# design.net
KiCad netlist of a schematic drawn in Altium Designer
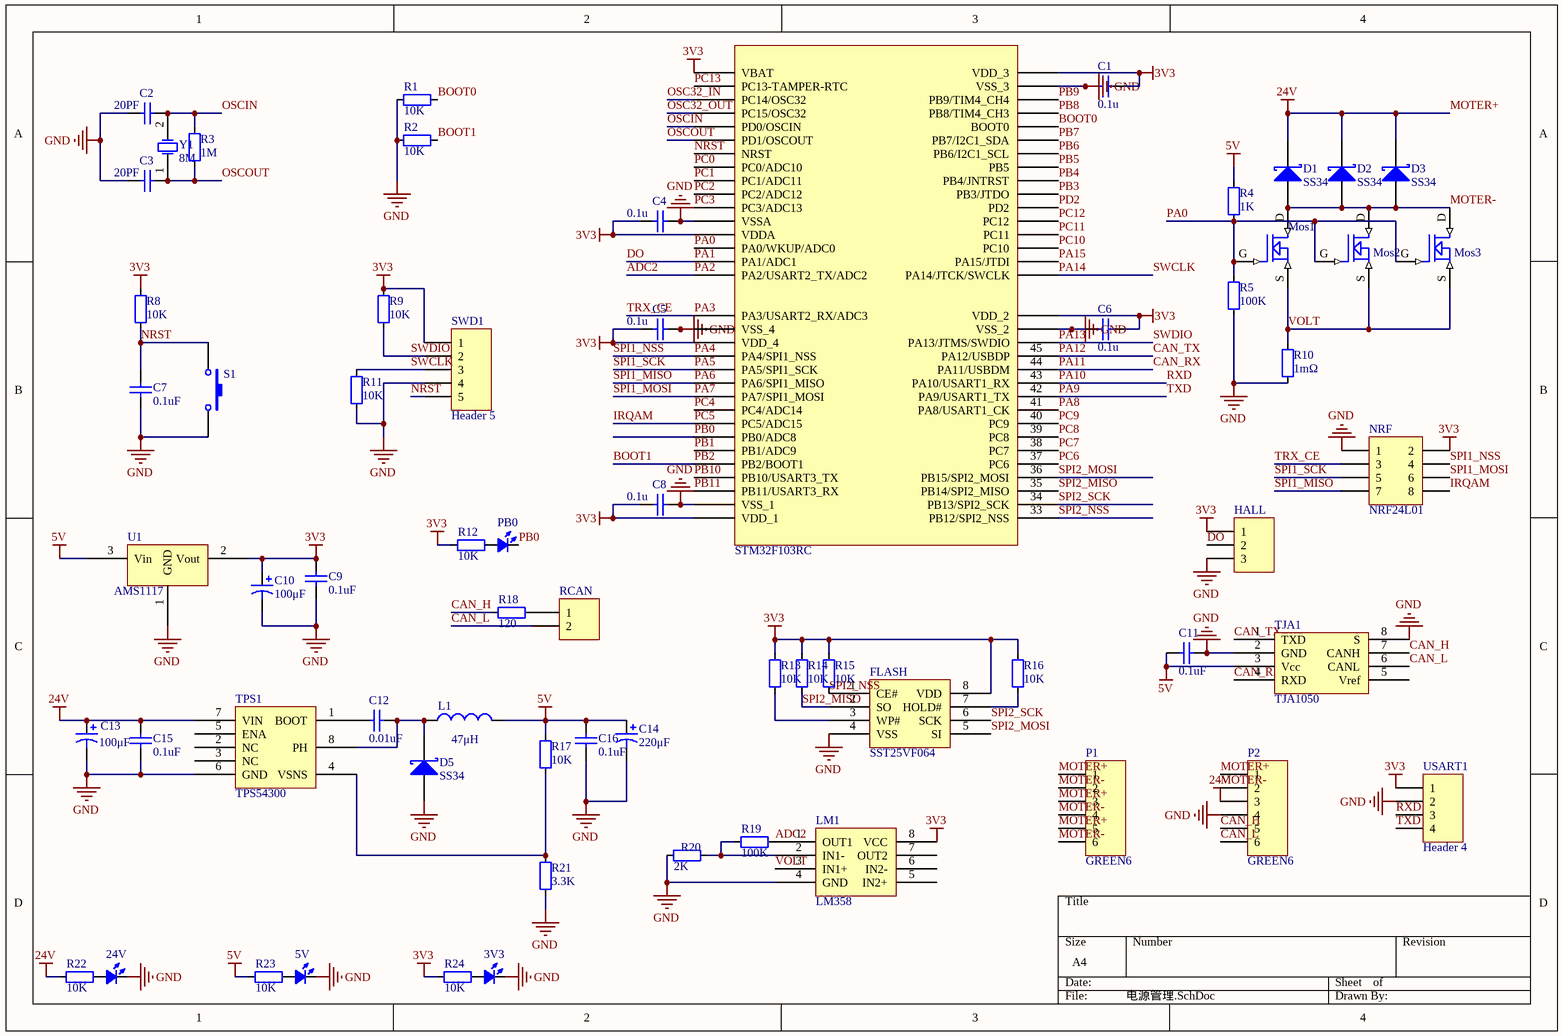
[diagram p0: 电源管理.SchDoc]

(export (version "E")
  (design (tool "Eeschema 10.0.6"))
  (components
    (comp (ref "3V3")
      (value "LED_0603")
      (footprint "LED_0805_GREEN")
      (description "LED")
      (libsource (lib "Integrated_Library") (part "LED_0603"))
    )
    (comp (ref "5V")
      (value "LED_0603")
      (footprint "LED_0805_GREEN")
      (description "LED")
      (libsource (lib "Integrated_Library") (part "LED_0603"))
    )
    (comp (ref "24V")
      (value "LED_0603")
      (footprint "LED_0805_GREEN")
      (description "LED")
      (libsource (lib "Integrated_Library") (part "LED_0603"))
    )
    (comp (ref "C1")
      (value "0.1u")
      (footprint "CAP-MLCC-0603")
      (description "Capacitor")
      (fields (field (name "Comment") "Cap") (field (name "PUBLISHER") "Altium Limited"))
      (libsource (lib "K60-mainboard-v3.1") (part "Cap_1"))
    )
    (comp (ref "C2")
      (value "20PF")
      (footprint "CAP-MLCC-0603")
      (description "Capacitor")
      (fields (field (name "Comment") "Cap") (field (name "PUBLISHER") "Altium Limited"))
      (libsource (lib "K60-mainboard-v3.1") (part "Cap_1"))
    )
    (comp (ref "C3")
      (value "20PF")
      (footprint "CAP-MLCC-0603")
      (description "Capacitor")
      (fields (field (name "Comment") "Cap") (field (name "PUBLISHER") "Altium Limited"))
      (libsource (lib "K60-mainboard-v3.1") (part "Cap_1"))
    )
    (comp (ref "C4")
      (value "0.1u")
      (footprint "CAP-MLCC-0603")
      (description "Capacitor")
      (fields (field (name "Comment") "Cap") (field (name "PUBLISHER") "Altium Limited"))
      (libsource (lib "K60-mainboard-v3.1") (part "Cap_1"))
    )
    (comp (ref "C5")
      (value "0.1u")
      (footprint "CAP-MLCC-0603")
      (description "Capacitor")
      (fields (field (name "Comment") "Cap") (field (name "PUBLISHER") "Altium Limited"))
      (libsource (lib "K60-mainboard-v3.1") (part "Cap_1"))
    )
    (comp (ref "C6")
      (value "0.1u")
      (footprint "CAP-MLCC-0603")
      (description "Capacitor")
      (fields (field (name "Comment") "Cap") (field (name "PUBLISHER") "Altium Limited"))
      (libsource (lib "K60-mainboard-v3.1") (part "Cap_1"))
    )
    (comp (ref "C7")
      (value "0.1uF")
      (footprint "CAP-MLCC-0603")
      (description "Capacitor")
      (fields (field (name "Comment") "Cap") (field (name "PUBLISHER") "Altium Limited"))
      (libsource (lib "K60-mainboard-v3.1") (part "Cap"))
    )
    (comp (ref "C8")
      (value "0.1u")
      (footprint "CAP-MLCC-0603")
      (description "Capacitor")
      (fields (field (name "Comment") "Cap") (field (name "PUBLISHER") "Altium Limited"))
      (libsource (lib "K60-mainboard-v3.1") (part "Cap_1"))
    )
    (comp (ref "C9")
      (value "0.1uF")
      (footprint "CAP-MLCC-0603")
      (description "Capacitor")
      (fields (field (name "Comment") "Cap") (field (name "PUBLISHER") "Altium Limited"))
      (libsource (lib "K60-mainboard-v3.1") (part "Cap"))
    )
    (comp (ref "C10")
      (value "100μF")
      (footprint "CAP-TAN-3216/CAPA")
      (description "钽电容")
      (fields (field (name "PUBLISHER") "Altium Limited"))
      (libsource (lib "Libraries_2014_0618") (part "CAP-TAN"))
    )
    (comp (ref "C11")
      (value "0.1uF")
      (footprint "CAP-MLCC-0603")
      (description "Capacitor")
      (fields (field (name "Comment") "Cap") (field (name "PUBLISHER") "Altium Limited"))
      (libsource (lib "K60-mainboard-v3.1") (part "Cap"))
    )
    (comp (ref "C12")
      (value "0.01uF")
      (footprint "CAP-MLCC-0603")
      (description "Capacitor")
      (fields (field (name "Comment") "Cap") (field (name "PUBLISHER") "Altium Limited"))
      (libsource (lib "K60-mainboard-v3.1") (part "Cap"))
    )
    (comp (ref "C13")
      (value "100μF")
      (footprint "C5:C5")
      (description "钽电容")
      (fields (field (name "PUBLISHER") "Altium Limited"))
      (libsource (lib "Libraries_2014_0618") (part "CAP-TAN"))
    )
    (comp (ref "C14")
      (value "220μF")
      (footprint "CAP-TAN-7343/CAPD")
      (description "钽电容")
      (fields (field (name "PUBLISHER") "Altium Limited"))
      (libsource (lib "Libraries_2014_0618") (part "CAP-TAN"))
    )
    (comp (ref "C15")
      (value "0.1uF")
      (footprint "CAP-MLCC-0603")
      (description "Capacitor")
      (fields (field (name "Comment") "Cap") (field (name "PUBLISHER") "Altium Limited"))
      (libsource (lib "K60-mainboard-v3.1") (part "Cap"))
    )
    (comp (ref "C16")
      (value "0.1uF")
      (footprint "CAP-MLCC-0603")
      (description "Capacitor")
      (fields (field (name "Comment") "Cap") (field (name "PUBLISHER") "Altium Limited"))
      (libsource (lib "K60-mainboard-v3.1") (part "Cap"))
    )
    (comp (ref "D1")
      (value "SS34")
      (footprint "DO-214AC")
      (description "肖特基二极管")
      (fields (field (name "PUBLISHER") "Altium Limited"))
      (libsource (lib "Libraries_2014_0618") (part "DIODE-Schottky"))
    )
    (comp (ref "D2")
      (value "SS34")
      (footprint "DO-214AC")
      (description "肖特基二极管")
      (fields (field (name "PUBLISHER") "Altium Limited"))
      (libsource (lib "Libraries_2014_0618") (part "DIODE-Schottky"))
    )
    (comp (ref "D3")
      (value "SS34")
      (footprint "DO-214AC")
      (description "肖特基二极管")
      (fields (field (name "PUBLISHER") "Altium Limited"))
      (libsource (lib "Libraries_2014_0618") (part "DIODE-Schottky"))
    )
    (comp (ref "D5")
      (value "SS34")
      (footprint "DO-214AC")
      (description "肖特基二极管")
      (fields (field (name "PUBLISHER") "Altium Limited"))
      (libsource (lib "Libraries_2014_0618") (part "DIODE-Schottky"))
    )
    (comp (ref "FLASH")
      (value "SST25VF064")
      (footprint "SOIC_E200_8")
      (libsource (lib "SST25VF064") (part "Component_1"))
    )
    (comp (ref "HALL")
      (value "Header 3")
      (footprint "HDR1X3")
      (description "Header, 3-Pin")
      (fields (field (name "PUBLISHER") "Altium Limited"))
      (libsource (lib "Libraries_2014_0618") (part "Header 3"))
    )
    (comp (ref "L1")
      (value "47μH")
      (footprint "Integrated_Library:IND_CD32")
      (description "Inductor")
      (fields (field (name "PUBLISHER") "Altium Limited"))
      (libsource (lib "Miscellaneous Devices") (part "Inductor"))
    )
    (comp (ref "LM1")
      (value "LM358")
      (footprint "PCB_IntegratedCircuit:SOP_E150_8")
      (libsource (lib "LM358") (part "Component_1"))
    )
    (comp (ref "Mos1")
      (value "MOSFET N")
      (footprint "Integrated_Library:TO-252AA")
      (description "MOS SOT23")
      (libsource (lib "Integrated_Library") (part "MOSFET N"))
    )
    (comp (ref "Mos2")
      (value "MOSFET N")
      (footprint "Integrated_Library:TO-252AA")
      (description "MOS SOT23")
      (libsource (lib "Integrated_Library") (part "MOSFET N"))
    )
    (comp (ref "Mos3")
      (value "MOSFET N")
      (footprint "Integrated_Library:TO-252AA")
      (description "MOS SOT23")
      (libsource (lib "Integrated_Library") (part "MOSFET N"))
    )
    (comp (ref "NRF")
      (value "NRF24L01")
      (footprint "HDR2X4")
      (description "Header, 4-Pin, Dual row")
      (fields (field (name "PUBLISHER") "Altium Limited"))
      (libsource (lib "Miscellaneous Connectors") (part "MHDR2X4"))
    )
    (comp (ref "P1")
      (value "GREEN6")
      (footprint "Green_6P")
      (description "Header, 6-Pin")
      (fields (field (name "PUBLISHER") "Altium Limited"))
      (libsource (lib "Libraries_2014_0618") (part "Header 6"))
    )
    (comp (ref "P2")
      (value "GREEN6")
      (footprint "Green_6P")
      (description "Header, 6-Pin")
      (fields (field (name "PUBLISHER") "Altium Limited"))
      (libsource (lib "Libraries_2014_0618") (part "Header 6"))
    )
    (comp (ref "PB0")
      (value "LED_0603")
      (footprint "LED_0805_GREEN")
      (description "LED")
      (libsource (lib "Integrated_Library") (part "LED_0603"))
    )
    (comp (ref "R1")
      (value "10K")
      (footprint "RES-0603")
      (description "Resistor")
      (fields (field (name "Comment") "Res_0603"))
      (libsource (lib "Integrated_Library") (part "Res_0603"))
    )
    (comp (ref "R2")
      (value "10K")
      (footprint "RES-0603")
      (description "Resistor")
      (fields (field (name "Comment") "Res_0603"))
      (libsource (lib "Integrated_Library") (part "Res_0603"))
    )
    (comp (ref "R3")
      (value "1M")
      (footprint "RES-0603")
      (description "Resistor")
      (fields (field (name "Comment") "Res_0603"))
      (libsource (lib "") (part "Res_0603_1"))
    )
    (comp (ref "R4")
      (value "1K")
      (footprint "RES-0603")
      (description "Resistor")
      (fields (field (name "Comment") "Res_0603"))
      (libsource (lib "") (part "Res_0603_1"))
    )
    (comp (ref "R5")
      (value "100K")
      (footprint "RES-0603")
      (description "Resistor")
      (fields (field (name "Comment") "Res_0603"))
      (libsource (lib "") (part "Res_0603_1"))
    )
    (comp (ref "R8")
      (value "10K")
      (footprint "RES-0603")
      (description "Resistor")
      (fields (field (name "Comment") "Res_0603"))
      (libsource (lib "") (part "Res_0603_1"))
    )
    (comp (ref "R9")
      (value "10K")
      (footprint "RES-0603")
      (description "Resistor")
      (fields (field (name "Comment") "Res_0603"))
      (libsource (lib "") (part "Res_0603_1"))
    )
    (comp (ref "R10")
      (value "1mΩ")
      (footprint "RESC6332")
      (description "Resistor")
      (fields (field (name "Comment") "Res_0603"))
      (libsource (lib "") (part "Res_0603_1"))
    )
    (comp (ref "R11")
      (value "10K")
      (footprint "RES-0603")
      (description "Resistor")
      (fields (field (name "Comment") "Res_0603"))
      (libsource (lib "") (part "Res_0603_1"))
    )
    (comp (ref "R12")
      (value "10K")
      (footprint "RES-0603")
      (description "Resistor")
      (fields (field (name "Comment") "Res_0603"))
      (libsource (lib "Integrated_Library") (part "Res_0603"))
    )
    (comp (ref "R13")
      (value "10K")
      (footprint "RES-0603")
      (description "Resistor")
      (fields (field (name "Comment") "Res_0603"))
      (libsource (lib "") (part "Res_0603_1"))
    )
    (comp (ref "R14")
      (value "10K")
      (footprint "RES-0603")
      (description "Resistor")
      (fields (field (name "Comment") "Res_0603"))
      (libsource (lib "") (part "Res_0603_1"))
    )
    (comp (ref "R15")
      (value "10K")
      (footprint "RES-0603")
      (description "Resistor")
      (fields (field (name "Comment") "Res_0603"))
      (libsource (lib "") (part "Res_0603_1"))
    )
    (comp (ref "R16")
      (value "10K")
      (footprint "RES-0603")
      (description "Resistor")
      (fields (field (name "Comment") "Res_0603"))
      (libsource (lib "") (part "Res_0603_1"))
    )
    (comp (ref "R17")
      (value "10K")
      (footprint "RES-0603")
      (description "Resistor")
      (fields (field (name "Comment") "Res_0603"))
      (libsource (lib "") (part "Res_0603_1"))
    )
    (comp (ref "R18")
      (value "120")
      (footprint "RES-0603")
      (description "Resistor")
      (fields (field (name "Comment") "Res_0603"))
      (libsource (lib "Integrated_Library") (part "Res_0603"))
    )
    (comp (ref "R19")
      (value "100K")
      (footprint "RES-0603")
      (description "Resistor")
      (fields (field (name "Comment") "Res_0603"))
      (libsource (lib "") (part "Res_0603_3"))
    )
    (comp (ref "R20")
      (value "2K")
      (footprint "RES-0603")
      (description "Resistor")
      (fields (field (name "Comment") "Res_0603"))
      (libsource (lib "") (part "Res_0603_3"))
    )
    (comp (ref "R21")
      (value "3.3K")
      (footprint "RES-0603")
      (description "Resistor")
      (fields (field (name "Comment") "Res_0603"))
      (libsource (lib "") (part "Res_0603_2"))
    )
    (comp (ref "R22")
      (value "10K")
      (footprint "RES-0603")
      (description "Resistor")
      (fields (field (name "Comment") "Res_0603"))
      (libsource (lib "Integrated_Library") (part "Res_0603"))
    )
    (comp (ref "R23")
      (value "10K")
      (footprint "RES-0603")
      (description "Resistor")
      (fields (field (name "Comment") "Res_0603"))
      (libsource (lib "Integrated_Library") (part "Res_0603"))
    )
    (comp (ref "R24")
      (value "10K")
      (footprint "RES-0603")
      (description "Resistor")
      (fields (field (name "Comment") "Res_0603"))
      (libsource (lib "Integrated_Library") (part "Res_0603"))
    )
    (comp (ref "RCAN")
      (value "~")
      (footprint "HDR1X2")
      (description "Header, 2-Pin")
      (fields (field (name "PUBLISHER") "Altium Limited"))
      (libsource (lib "Miscellaneous Connectors") (part "Header 2"))
    )
    (comp (ref "S1")
      (value "SW-PB")
      (footprint "PCB_Switch:KEY_SMD")
      (description "按钮")
      (fields (field (name "PUBLISHER") "Altium Limited"))
      (libsource (lib "Libraries_2014_0618") (part "SW-PB"))
    )
    (comp (ref "STM32F103RC")
      (value "STM32F103RC")
      (footprint "LQFP_P0.5_64")
      (description "MCU")
      (libsource (lib "Integrated_Library") (part "STM32F103RC"))
    )
    (comp (ref "SWD1")
      (value "Header 5")
      (footprint "HDR1X5")
      (description "Header, 5-Pin")
      (fields (field (name "PUBLISHER") "Altium Limited"))
      (libsource (lib "K60-mainboard-v3.1") (part "Header 5"))
    )
    (comp (ref "TJA1")
      (value "TJA1050")
      (footprint "TJA1050")
      (description "CAN总线收发器")
      (libsource (lib "Libraries_2014_0618") (part "TJA1050"))
    )
    (comp (ref "TPS1")
      (value "TPS54300")
      (footprint "SOP_E150_8")
      (libsource (lib "TPS54300") (part "TPS54300"))
    )
    (comp (ref "U1") (value "AMS1117") (footprint "SOT223-3") (libsource (lib "AMS1117") (part "AMS１１１７")))
    (comp (ref "USART1")
      (value "Header 4")
      (footprint "HDR1X4")
      (description "Header, 4-Pin")
      (fields (field (name "PUBLISHER") "Altium Limited"))
      (libsource (lib "K60-mainboard-v3.1") (part "Header 4"))
    )
    (comp (ref "Y1")
      (value "8M")
      (footprint "Libraries_2014_0618:Osc-6032")
      (description "Crystal Oscillator")
      (fields (field (name "PUBLISHER") "Altium Limited"))
      (libsource (lib "Libraries_2014_0618") (part "C-Osc"))
    )
  )
  (nets
    (net (code "1") (name "/ADC2") (class "Default")
      (node (ref "LM1") (pin "1") (pinfunction "OUT1_1") (pintype "passive"))
      (node (ref "R19") (pin "2") (pinfunction "2_2") (pintype "passive"))
      (node (ref "STM32F103RC") (pin "16") (pinfunction "PA2/USART2_TX/ADC2_16") (pintype "passive"))
    )
    (net (code "2") (name "/BOOT0") (class "Default")
      (node (ref "R1") (pin "1") (pinfunction "1_1") (pintype "passive"))
      (node (ref "STM32F103RC") (pin "60") (pinfunction "BOOT0_60") (pintype "passive"))
    )
    (net (code "3") (name "/BOOT1") (class "Default")
      (node (ref "R2") (pin "1") (pinfunction "1_1") (pintype "passive"))
      (node (ref "STM32F103RC") (pin "28") (pinfunction "PB2/BOOT1_28") (pintype "passive"))
    )
    (net (code "4") (name "/CAN_H") (class "Default")
      (node (ref "P2") (pin "5") (pinfunction "5_5") (pintype "passive"))
      (node (ref "R18") (pin "2") (pinfunction "2_2") (pintype "passive"))
      (node (ref "TJA1") (pin "7") (pinfunction "CANH_7") (pintype "passive"))
    )
    (net (code "5") (name "/CAN_L") (class "Default")
      (node (ref "P2") (pin "6") (pinfunction "6_6") (pintype "passive"))
      (node (ref "RCAN") (pin "2") (pinfunction "2_2") (pintype "passive"))
      (node (ref "TJA1") (pin "6") (pinfunction "CANL_6") (pintype "passive"))
    )
    (net (code "6") (name "/CAN_RX") (class "Default")
      (node (ref "STM32F103RC") (pin "44") (pinfunction "PA11/USBDM_44") (pintype "passive"))
      (node (ref "TJA1") (pin "4") (pinfunction "RXD_4") (pintype "passive"))
    )
    (net (code "7") (name "/CAN_TX") (class "Default")
      (node (ref "STM32F103RC") (pin "45") (pinfunction "PA12/USBDP_45") (pintype "passive"))
      (node (ref "TJA1") (pin "1") (pinfunction "TXD_1") (pintype "passive"))
    )
    (net (code "8") (name "/DO") (class "Default")
      (node (ref "HALL") (pin "2") (pinfunction "2_2") (pintype "passive"))
      (node (ref "STM32F103RC") (pin "15") (pinfunction "PA1/ADC1_15") (pintype "passive"))
    )
    (net (code "9") (name "/IRQAM") (class "Default")
      (node (ref "NRF") (pin "8") (pinfunction "8_8") (pintype "passive"))
      (node (ref "STM32F103RC") (pin "25") (pinfunction "PC5/ADC15_25") (pintype "passive"))
    )
    (net (code "10") (name "/MOTER-") (class "Default")
      (node (ref "D1") (pin "1") (pinfunction "A_1") (pintype "passive"))
      (node (ref "D2") (pin "1") (pinfunction "A_1") (pintype "passive"))
      (node (ref "D3") (pin "1") (pinfunction "A_1") (pintype "passive"))
      (node (ref "Mos1") (pin "D") (pinfunction "D_D") (pintype "input"))
      (node (ref "Mos2") (pin "D") (pinfunction "D_D") (pintype "input"))
      (node (ref "Mos3") (pin "D") (pinfunction "D_D") (pintype "input"))
      (node (ref "P1") (pin "2") (pinfunction "2_2") (pintype "passive"))
      (node (ref "P1") (pin "4") (pinfunction "4_4") (pintype "passive"))
      (node (ref "P1") (pin "6") (pinfunction "6_6") (pintype "passive"))
      (node (ref "P2") (pin "2") (pinfunction "2_2") (pintype "passive"))
    )
    (net (code "11") (name "/NRST") (class "Default")
      (node (ref "C7") (pin "1") (pinfunction "1_1") (pintype "passive"))
      (node (ref "R8") (pin "1") (pinfunction "1_1") (pintype "passive"))
      (node (ref "S1") (pin "1") (pinfunction "1_1") (pintype "passive"))
      (node (ref "STM32F103RC") (pin "7") (pinfunction "NRST_7") (pintype "passive"))
      (node (ref "SWD1") (pin "5") (pinfunction "5_5") (pintype "passive"))
    )
    (net (code "12") (name "/OSC32_IN") (class "Default")
      (node (ref "STM32F103RC") (pin "3") (pinfunction "PC14/OSC32_3") (pintype "passive"))
    )
    (net (code "13") (name "/OSC32_OUT") (class "Default")
      (node (ref "STM32F103RC") (pin "4") (pinfunction "PC15/OSC32_4") (pintype "passive"))
    )
    (net (code "14") (name "/OSCIN") (class "Default")
      (node (ref "C2") (pin "2") (pinfunction "2_2") (pintype "passive"))
      (node (ref "R3") (pin "2") (pinfunction "2_2") (pintype "passive"))
      (node (ref "STM32F103RC") (pin "5") (pinfunction "PD0/OSCIN_5") (pintype "passive"))
      (node (ref "Y1") (pin "2") (pinfunction "OSC2_2") (pintype "passive"))
    )
    (net (code "15") (name "/OSCOUT") (class "Default")
      (node (ref "C3") (pin "2") (pinfunction "2_2") (pintype "passive"))
      (node (ref "R3") (pin "1") (pinfunction "1_1") (pintype "passive"))
      (node (ref "STM32F103RC") (pin "6") (pinfunction "PD1/OSCOUT_6") (pintype "passive"))
      (node (ref "Y1") (pin "1") (pinfunction "OSC1_1") (pintype "passive"))
    )
    (net (code "16") (name "/PA0") (class "Default")
      (node (ref "Mos1") (pin "G") (pinfunction "G_G") (pintype "input"))
      (node (ref "Mos2") (pin "G") (pinfunction "G_G") (pintype "input"))
      (node (ref "Mos3") (pin "G") (pinfunction "G_G") (pintype "input"))
      (node (ref "R4") (pin "1") (pinfunction "1_1") (pintype "passive"))
      (node (ref "R5") (pin "2") (pinfunction "2_2") (pintype "passive"))
      (node (ref "STM32F103RC") (pin "14") (pinfunction "PA0/WKUP/ADC0_14") (pintype "passive"))
    )
    (net (code "17") (name "/PA3") (class "Default")
      (node (ref "NRF") (pin "3") (pinfunction "3_3") (pintype "passive"))
      (node (ref "STM32F103RC") (pin "17") (pinfunction "PA3/USART2_RX/ADC3_17") (pintype "passive"))
    )
    (net (code "18") (name "/PA4") (class "Default")
      (node (ref "NRF") (pin "4") (pinfunction "4_4") (pintype "passive"))
      (node (ref "STM32F103RC") (pin "20") (pinfunction "PA4/SPI1_NSS_20") (pintype "passive"))
    )
    (net (code "19") (name "/PA5") (class "Default")
      (node (ref "NRF") (pin "5") (pinfunction "5_5") (pintype "passive"))
      (node (ref "STM32F103RC") (pin "21") (pinfunction "PA5/SPI1_SCK_21") (pintype "passive"))
    )
    (net (code "20") (name "/PA6") (class "Default")
      (node (ref "NRF") (pin "7") (pinfunction "7_7") (pintype "passive"))
      (node (ref "STM32F103RC") (pin "22") (pinfunction "PA6/SPI1_MISO_22") (pintype "passive"))
    )
    (net (code "21") (name "/PA7") (class "Default")
      (node (ref "NRF") (pin "6") (pinfunction "6_6") (pintype "passive"))
      (node (ref "STM32F103RC") (pin "23") (pinfunction "PA7/SPI1_MOSI_23") (pintype "passive"))
    )
    (net (code "22") (name "/PA8") (class "Default")
      (node (ref "STM32F103RC") (pin "41") (pinfunction "PA8/USART1_CK_41") (pintype "passive"))
    )
    (net (code "23") (name "/PA9") (class "Default")
      (node (ref "STM32F103RC") (pin "42") (pinfunction "PA9/USART1_TX_42") (pintype "passive"))
      (node (ref "USART1") (pin "4") (pinfunction "4_4") (pintype "passive"))
    )
    (net (code "24") (name "/PA10") (class "Default")
      (node (ref "STM32F103RC") (pin "43") (pinfunction "PA10/USART1_RX_43") (pintype "passive"))
      (node (ref "USART1") (pin "3") (pinfunction "3_3") (pintype "passive"))
    )
    (net (code "25") (name "/PA13") (class "Default")
      (node (ref "R9") (pin "1") (pinfunction "1_1") (pintype "passive"))
      (node (ref "STM32F103RC") (pin "46") (pinfunction "PA13/JTMS/SWDIO_46") (pintype "passive"))
      (node (ref "SWD1") (pin "2") (pinfunction "2_2") (pintype "passive"))
    )
    (net (code "26") (name "/PA14") (class "Default")
      (node (ref "R11") (pin "2") (pinfunction "2_2") (pintype "passive"))
      (node (ref "STM32F103RC") (pin "49") (pinfunction "PA14/JTCK/SWCLK_49") (pintype "passive"))
      (node (ref "SWD1") (pin "3") (pinfunction "3_3") (pintype "passive"))
    )
    (net (code "27") (name "/PA15") (class "Default")
      (node (ref "STM32F103RC") (pin "50") (pinfunction "PA15/JTDI_50") (pintype "passive"))
    )
    (net (code "28") (name "/PB0") (class "Default")
      (node (ref "PB0") (pin "2") (pinfunction "K_2") (pintype "passive"))
      (node (ref "STM32F103RC") (pin "26") (pinfunction "PB0/ADC8_26") (pintype "passive"))
    )
    (net (code "29") (name "/PB1") (class "Default")
      (node (ref "STM32F103RC") (pin "27") (pinfunction "PB1/ADC9_27") (pintype "passive"))
    )
    (net (code "30") (name "/PB3") (class "Default")
      (node (ref "STM32F103RC") (pin "55") (pinfunction "PB3/JTDO_55") (pintype "passive"))
    )
    (net (code "31") (name "/PB4") (class "Default")
      (node (ref "STM32F103RC") (pin "56") (pinfunction "PB4/JNTRST_56") (pintype "passive"))
    )
    (net (code "32") (name "/PB5") (class "Default")
      (node (ref "STM32F103RC") (pin "57") (pinfunction "PB5_57") (pintype "passive"))
    )
    (net (code "33") (name "/PB6") (class "Default")
      (node (ref "STM32F103RC") (pin "58") (pinfunction "PB6/I2C1_SCL_58") (pintype "passive"))
    )
    (net (code "34") (name "/PB7") (class "Default")
      (node (ref "STM32F103RC") (pin "59") (pinfunction "PB7/I2C1_SDA_59") (pintype "passive"))
    )
    (net (code "35") (name "/PB8") (class "Default")
      (node (ref "STM32F103RC") (pin "61") (pinfunction "PB8/TIM4_CH3_61") (pintype "passive"))
    )
    (net (code "36") (name "/PB9") (class "Default")
      (node (ref "STM32F103RC") (pin "62") (pinfunction "PB9/TIM4_CH4_62") (pintype "passive"))
    )
    (net (code "37") (name "/PB10") (class "Default")
      (node (ref "STM32F103RC") (pin "29") (pinfunction "PB10/USART3_TX_29") (pintype "passive"))
    )
    (net (code "38") (name "/PB11") (class "Default")
      (node (ref "STM32F103RC") (pin "30") (pinfunction "PB11/USART3_RX_30") (pintype "passive"))
    )
    (net (code "39") (name "/PC0") (class "Default")
      (node (ref "STM32F103RC") (pin "8") (pinfunction "PC0/ADC10_8") (pintype "passive"))
    )
    (net (code "40") (name "/PC1") (class "Default")
      (node (ref "STM32F103RC") (pin "9") (pinfunction "PC1/ADC11_9") (pintype "passive"))
    )
    (net (code "41") (name "/PC2") (class "Default")
      (node (ref "STM32F103RC") (pin "10") (pinfunction "PC2/ADC12_10") (pintype "passive"))
    )
    (net (code "42") (name "/PC3") (class "Default")
      (node (ref "STM32F103RC") (pin "11") (pinfunction "PC3/ADC13_11") (pintype "passive"))
    )
    (net (code "43") (name "/PC4") (class "Default")
      (node (ref "STM32F103RC") (pin "24") (pinfunction "PC4/ADC14_24") (pintype "passive"))
    )
    (net (code "44") (name "/PC6") (class "Default")
      (node (ref "STM32F103RC") (pin "37") (pinfunction "PC6_37") (pintype "passive"))
    )
    (net (code "45") (name "/PC7") (class "Default")
      (node (ref "STM32F103RC") (pin "38") (pinfunction "PC7_38") (pintype "passive"))
    )
    (net (code "46") (name "/PC8") (class "Default")
      (node (ref "STM32F103RC") (pin "39") (pinfunction "PC8_39") (pintype "passive"))
    )
    (net (code "47") (name "/PC9") (class "Default")
      (node (ref "STM32F103RC") (pin "40") (pinfunction "PC9_40") (pintype "passive"))
    )
    (net (code "48") (name "/PC10") (class "Default")
      (node (ref "STM32F103RC") (pin "51") (pinfunction "PC10_51") (pintype "passive"))
    )
    (net (code "49") (name "/PC11") (class "Default")
      (node (ref "STM32F103RC") (pin "52") (pinfunction "PC11_52") (pintype "passive"))
    )
    (net (code "50") (name "/PC12") (class "Default")
      (node (ref "STM32F103RC") (pin "53") (pinfunction "PC12_53") (pintype "passive"))
    )
    (net (code "51") (name "/PC13") (class "Default")
      (node (ref "STM32F103RC") (pin "2") (pinfunction "PC13-TAMPER-RTC_2") (pintype "passive"))
    )
    (net (code "52") (name "/PD2") (class "Default")
      (node (ref "STM32F103RC") (pin "54") (pinfunction "PD2_54") (pintype "passive"))
    )
    (net (code "53") (name "/SPI2_MISO") (class "Default")
      (node (ref "FLASH") (pin "2") (pinfunction "SO_2") (pintype "passive"))
      (node (ref "R14") (pin "1") (pinfunction "1_1") (pintype "passive"))
      (node (ref "STM32F103RC") (pin "35") (pinfunction "PB14/SPI2_MISO_35") (pintype "passive"))
    )
    (net (code "54") (name "/SPI2_MOSI") (class "Default")
      (node (ref "FLASH") (pin "5") (pinfunction "SI_5") (pintype "passive"))
      (node (ref "STM32F103RC") (pin "36") (pinfunction "PB15/SPI2_MOSI_36") (pintype "passive"))
    )
    (net (code "55") (name "/SPI2_NSS") (class "Default")
      (node (ref "FLASH") (pin "1") (pinfunction "CE#_1") (pintype "passive"))
      (node (ref "R15") (pin "1") (pinfunction "1_1") (pintype "passive"))
      (node (ref "STM32F103RC") (pin "33") (pinfunction "PB12/SPI2_NSS_33") (pintype "passive"))
    )
    (net (code "56") (name "/SPI2_SCK") (class "Default")
      (node (ref "FLASH") (pin "6") (pinfunction "SCK_6") (pintype "passive"))
      (node (ref "STM32F103RC") (pin "34") (pinfunction "PB13/SPI2_SCK_34") (pintype "passive"))
    )
    (net (code "57") (name "/VOLT") (class "Default")
      (node (ref "LM1") (pin "3") (pinfunction "IN1+_3") (pintype "passive"))
      (node (ref "Mos1") (pin "S") (pinfunction "S_S") (pintype "input"))
      (node (ref "Mos2") (pin "S") (pinfunction "S_S") (pintype "input"))
      (node (ref "Mos3") (pin "S") (pinfunction "S_S") (pintype "input"))
      (node (ref "R10") (pin "2") (pinfunction "2_2") (pintype "passive"))
    )
    (net (code "58") (name "3V3") (class "Default")
      (node (ref "C1") (pin "1") (pinfunction "1_1") (pintype "passive"))
      (node (ref "C10") (pin "1") (pinfunction "1_1") (pintype "passive"))
      (node (ref "C4") (pin "1") (pinfunction "1_1") (pintype "passive"))
      (node (ref "C5") (pin "1") (pinfunction "1_1") (pintype "passive"))
      (node (ref "C6") (pin "1") (pinfunction "1_1") (pintype "passive"))
      (node (ref "C8") (pin "1") (pinfunction "1_1") (pintype "passive"))
      (node (ref "C9") (pin "2") (pinfunction "2_2") (pintype "passive"))
      (node (ref "FLASH") (pin "8") (pinfunction "VDD_8") (pintype "passive"))
      (node (ref "HALL") (pin "1") (pinfunction "1_1") (pintype "passive"))
      (node (ref "LM1") (pin "8") (pinfunction "VCC_8") (pintype "passive"))
      (node (ref "NRF") (pin "2") (pinfunction "2_2") (pintype "passive"))
      (node (ref "R12") (pin "2") (pinfunction "2_2") (pintype "passive"))
      (node (ref "R13") (pin "2") (pinfunction "2_2") (pintype "passive"))
      (node (ref "R14") (pin "2") (pinfunction "2_2") (pintype "passive"))
      (node (ref "R15") (pin "2") (pinfunction "2_2") (pintype "passive"))
      (node (ref "R16") (pin "2") (pinfunction "2_2") (pintype "passive"))
      (node (ref "R24") (pin "2") (pinfunction "2_2") (pintype "passive"))
      (node (ref "R8") (pin "2") (pinfunction "2_2") (pintype "passive"))
      (node (ref "R9") (pin "2") (pinfunction "2_2") (pintype "passive"))
      (node (ref "STM32F103RC") (pin "1") (pinfunction "VBAT_1") (pintype "passive"))
      (node (ref "STM32F103RC") (pin "13") (pinfunction "VDDA_13") (pintype "passive"))
      (node (ref "STM32F103RC") (pin "19") (pinfunction "VDD_4_19") (pintype "passive"))
      (node (ref "STM32F103RC") (pin "32") (pinfunction "VDD_1_32") (pintype "passive"))
      (node (ref "STM32F103RC") (pin "48") (pinfunction "VDD_2_48") (pintype "passive"))
      (node (ref "STM32F103RC") (pin "64") (pinfunction "VDD_3_64") (pintype "passive"))
      (node (ref "SWD1") (pin "1") (pinfunction "1_1") (pintype "passive"))
      (node (ref "U1") (pin "2") (pinfunction "Vout_2") (pintype "passive"))
      (node (ref "USART1") (pin "1") (pinfunction "1_1") (pintype "passive"))
    )
    (net (code "59") (name "5V") (class "Default")
      (node (ref "C11") (pin "1") (pinfunction "1_1") (pintype "passive"))
      (node (ref "C14") (pin "1") (pinfunction "1_1") (pintype "passive"))
      (node (ref "C16") (pin "2") (pinfunction "2_2") (pintype "passive"))
      (node (ref "L1") (pin "2") (pinfunction "2_2") (pintype "passive"))
      (node (ref "R17") (pin "2") (pinfunction "2_2") (pintype "passive"))
      (node (ref "R23") (pin "2") (pinfunction "2_2") (pintype "passive"))
      (node (ref "R4") (pin "2") (pinfunction "2_2") (pintype "passive"))
      (node (ref "TJA1") (pin "3") (pinfunction "Vcc_3") (pintype "passive"))
      (node (ref "U1") (pin "3") (pinfunction "Vin_3") (pintype "passive"))
    )
    (net (code "60") (name "24V") (class "Default")
      (node (ref "C13") (pin "1") (pinfunction "1_1") (pintype "passive"))
      (node (ref "C15") (pin "2") (pinfunction "2_2") (pintype "passive"))
      (node (ref "D1") (pin "2") (pinfunction "K_2") (pintype "passive"))
      (node (ref "D2") (pin "2") (pinfunction "K_2") (pintype "passive"))
      (node (ref "D3") (pin "2") (pinfunction "K_2") (pintype "passive"))
      (node (ref "P1") (pin "1") (pinfunction "1_1") (pintype "passive"))
      (node (ref "P1") (pin "3") (pinfunction "3_3") (pintype "passive"))
      (node (ref "P1") (pin "5") (pinfunction "5_5") (pintype "passive"))
      (node (ref "P2") (pin "1") (pinfunction "1_1") (pintype "passive"))
      (node (ref "P2") (pin "3") (pinfunction "3_3") (pintype "passive"))
      (node (ref "R22") (pin "2") (pinfunction "2_2") (pintype "passive"))
      (node (ref "TPS1") (pin "7") (pinfunction "VIN_7") (pintype "passive"))
    )
    (net (code "61") (name "GND") (class "Default")
      (node (ref "24V") (pin "2") (pinfunction "K_2") (pintype "passive"))
      (node (ref "3V3") (pin "2") (pinfunction "K_2") (pintype "passive"))
      (node (ref "5V") (pin "2") (pinfunction "K_2") (pintype "passive"))
      (node (ref "C1") (pin "2") (pinfunction "2_2") (pintype "passive"))
      (node (ref "C10") (pin "2") (pinfunction "2_2") (pintype "passive"))
      (node (ref "C11") (pin "2") (pinfunction "2_2") (pintype "passive"))
      (node (ref "C13") (pin "2") (pinfunction "2_2") (pintype "passive"))
      (node (ref "C14") (pin "2") (pinfunction "2_2") (pintype "passive"))
      (node (ref "C15") (pin "1") (pinfunction "1_1") (pintype "passive"))
      (node (ref "C16") (pin "1") (pinfunction "1_1") (pintype "passive"))
      (node (ref "C2") (pin "1") (pinfunction "1_1") (pintype "passive"))
      (node (ref "C3") (pin "1") (pinfunction "1_1") (pintype "passive"))
      (node (ref "C4") (pin "2") (pinfunction "2_2") (pintype "passive"))
      (node (ref "C5") (pin "2") (pinfunction "2_2") (pintype "passive"))
      (node (ref "C6") (pin "2") (pinfunction "2_2") (pintype "passive"))
      (node (ref "C7") (pin "2") (pinfunction "2_2") (pintype "passive"))
      (node (ref "C8") (pin "2") (pinfunction "2_2") (pintype "passive"))
      (node (ref "C9") (pin "1") (pinfunction "1_1") (pintype "passive"))
      (node (ref "D5") (pin "1") (pinfunction "A_1") (pintype "passive"))
      (node (ref "FLASH") (pin "4") (pinfunction "VSS_4") (pintype "passive"))
      (node (ref "HALL") (pin "3") (pinfunction "3_3") (pintype "passive"))
      (node (ref "LM1") (pin "4") (pinfunction "GND_4") (pintype "passive"))
      (node (ref "NRF") (pin "1") (pinfunction "1_1") (pintype "passive"))
      (node (ref "P2") (pin "4") (pinfunction "4_4") (pintype "passive"))
      (node (ref "R1") (pin "2") (pinfunction "2_2") (pintype "passive"))
      (node (ref "R10") (pin "1") (pinfunction "1_1") (pintype "passive"))
      (node (ref "R11") (pin "1") (pinfunction "1_1") (pintype "passive"))
      (node (ref "R2") (pin "2") (pinfunction "2_2") (pintype "passive"))
      (node (ref "R20") (pin "1") (pinfunction "1_1") (pintype "passive"))
      (node (ref "R21") (pin "2") (pinfunction "2_2") (pintype "passive"))
      (node (ref "R5") (pin "1") (pinfunction "1_1") (pintype "passive"))
      (node (ref "S1") (pin "2") (pinfunction "2_2") (pintype "passive"))
      (node (ref "STM32F103RC") (pin "12") (pinfunction "VSSA_12") (pintype "passive"))
      (node (ref "STM32F103RC") (pin "18") (pinfunction "VSS_4_18") (pintype "passive"))
      (node (ref "STM32F103RC") (pin "31") (pinfunction "VSS_1_31") (pintype "passive"))
      (node (ref "STM32F103RC") (pin "47") (pinfunction "VSS_2_47") (pintype "passive"))
      (node (ref "STM32F103RC") (pin "63") (pinfunction "VSS_3_63") (pintype "passive"))
      (node (ref "SWD1") (pin "4") (pinfunction "4_4") (pintype "passive"))
      (node (ref "TJA1") (pin "2") (pinfunction "GND_2") (pintype "passive"))
      (node (ref "TJA1") (pin "8") (pinfunction "S_8") (pintype "passive"))
      (node (ref "TPS1") (pin "6") (pinfunction "GND_6") (pintype "passive"))
      (node (ref "U1") (pin "1") (pinfunction "GND_1") (pintype "passive"))
      (node (ref "USART1") (pin "2") (pinfunction "2_2") (pintype "passive"))
    )
    (net (code "62") (name "Net-(3V3-A)") (class "Default")
      (node (ref "3V3") (pin "1") (pinfunction "A_1") (pintype "passive"))
      (node (ref "R24") (pin "1") (pinfunction "1_1") (pintype "passive"))
    )
    (net (code "63") (name "Net-(5V-A)") (class "Default")
      (node (ref "5V") (pin "1") (pinfunction "A_1") (pintype "passive"))
      (node (ref "R23") (pin "1") (pinfunction "1_1") (pintype "passive"))
    )
    (net (code "64") (name "Net-(24V-A)") (class "Default")
      (node (ref "24V") (pin "1") (pinfunction "A_1") (pintype "passive"))
      (node (ref "R22") (pin "1") (pinfunction "1_1") (pintype "passive"))
    )
    (net (code "65") (name "Net-(D5-K)") (class "Default")
      (node (ref "C12") (pin "1") (pinfunction "1_1") (pintype "passive"))
      (node (ref "D5") (pin "2") (pinfunction "K_2") (pintype "passive"))
      (node (ref "L1") (pin "1") (pinfunction "1_1") (pintype "passive"))
      (node (ref "TPS1") (pin "8") (pinfunction "PH_8") (pintype "passive"))
    )
    (net (code "66") (name "Net-(FLASH-HOLD#)") (class "Default")
      (node (ref "FLASH") (pin "7") (pinfunction "HOLD#_7") (pintype "passive"))
      (node (ref "R16") (pin "1") (pinfunction "1_1") (pintype "passive"))
    )
    (net (code "67") (name "Net-(FLASH-WP#)") (class "Default")
      (node (ref "FLASH") (pin "3") (pinfunction "WP#_3") (pintype "passive"))
      (node (ref "R13") (pin "1") (pinfunction "1_1") (pintype "passive"))
    )
    (net (code "68") (name "Net-(LM1-IN1-)") (class "Default")
      (node (ref "LM1") (pin "2") (pinfunction "IN1-_2") (pintype "passive"))
      (node (ref "R19") (pin "1") (pinfunction "1_1") (pintype "passive"))
      (node (ref "R20") (pin "2") (pinfunction "2_2") (pintype "passive"))
    )
    (net (code "69") (name "Net-(PB0-A)") (class "Default")
      (node (ref "PB0") (pin "1") (pinfunction "A_1") (pintype "passive"))
      (node (ref "R12") (pin "1") (pinfunction "1_1") (pintype "passive"))
    )
    (net (code "70") (name "Net-(R18-Pad1)") (class "Default")
      (node (ref "R18") (pin "1") (pinfunction "1_1") (pintype "passive"))
      (node (ref "RCAN") (pin "1") (pinfunction "1_1") (pintype "passive"))
    )
    (net (code "71") (name "Net-(TPS1-BOOT)") (class "Default")
      (node (ref "C12") (pin "2") (pinfunction "2_2") (pintype "passive"))
      (node (ref "TPS1") (pin "1") (pinfunction "BOOT_1") (pintype "passive"))
    )
    (net (code "72") (name "Net-(TPS1-VSNS)") (class "Default")
      (node (ref "R17") (pin "1") (pinfunction "1_1") (pintype "passive"))
      (node (ref "R21") (pin "1") (pinfunction "1_1") (pintype "passive"))
      (node (ref "TPS1") (pin "4") (pinfunction "VSNS_4") (pintype "passive"))
    )
    (net (code "73") (name "unconnected-(LM1-IN2+-Pad5)") (class "Default")
      (node (ref "LM1") (pin "5") (pinfunction "IN2+_5") (pintype "passive"))
    )
    (net (code "74") (name "unconnected-(LM1-IN2--Pad6)") (class "Default")
      (node (ref "LM1") (pin "6") (pinfunction "IN2-_6") (pintype "passive"))
    )
    (net (code "75") (name "unconnected-(LM1-OUT2-Pad7)") (class "Default")
      (node (ref "LM1") (pin "7") (pinfunction "OUT2_7") (pintype "passive"))
    )
    (net (code "76") (name "unconnected-(TJA1-Vref-Pad5)") (class "Default")
      (node (ref "TJA1") (pin "5") (pinfunction "Vref_5") (pintype "passive"))
    )
    (net (code "77") (name "unconnected-(TPS1-ENA-Pad5)") (class "Default")
      (node (ref "TPS1") (pin "5") (pinfunction "ENA_5") (pintype "passive"))
    )
    (net (code "78") (name "unconnected-(TPS1-NC-Pad2)") (class "Default")
      (node (ref "TPS1") (pin "2") (pinfunction "NC_2") (pintype "passive"))
    )
    (net (code "79") (name "unconnected-(TPS1-NC-Pad3)") (class "Default")
      (node (ref "TPS1") (pin "3") (pinfunction "NC_3") (pintype "passive"))
    )
  )
)
